# NIR-Spec-Analog-SCH_SH2__01.net
KiCad netlist of a schematic drawn in Altium Designer
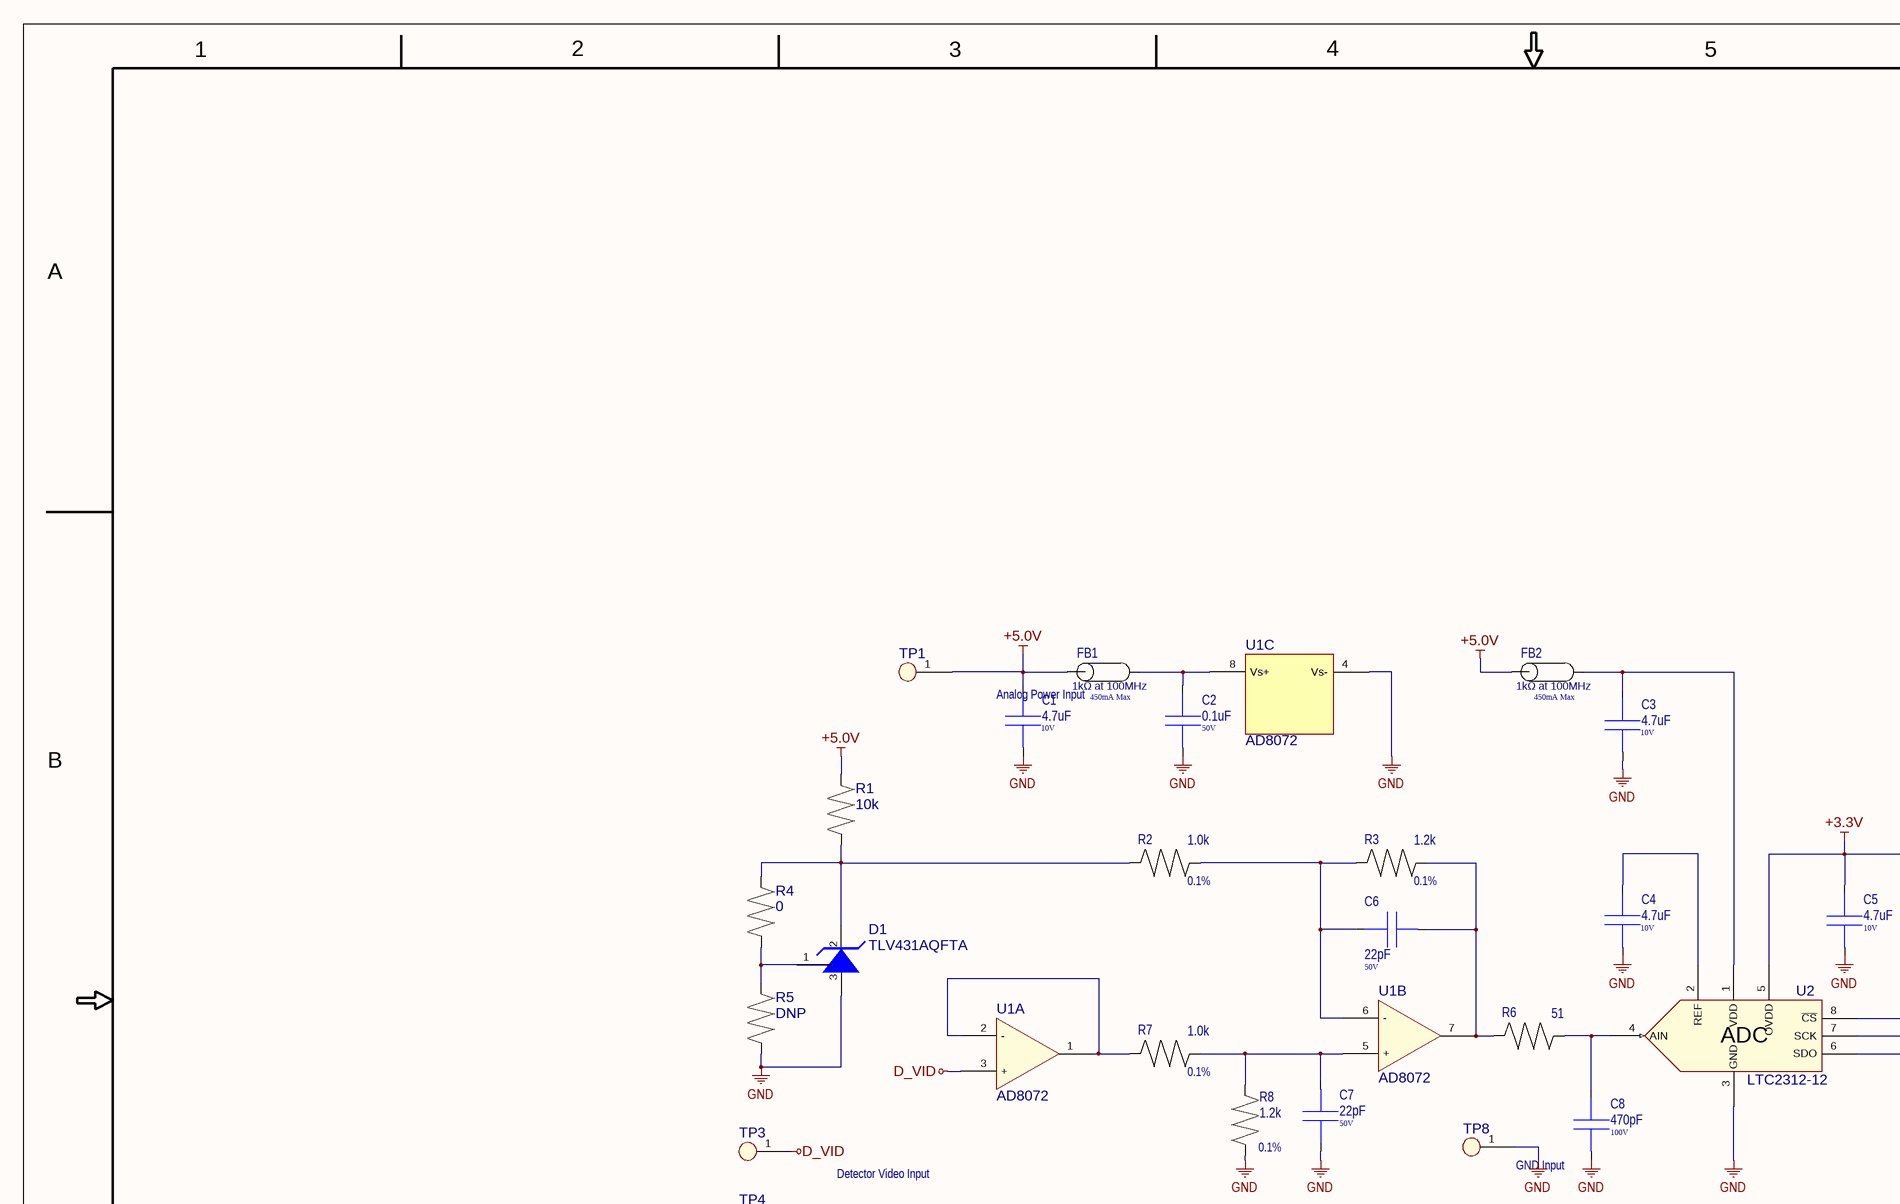
[diagram p0: NIR-Spec-Analog-SCH_SH2_(01).SchDoc, top left]
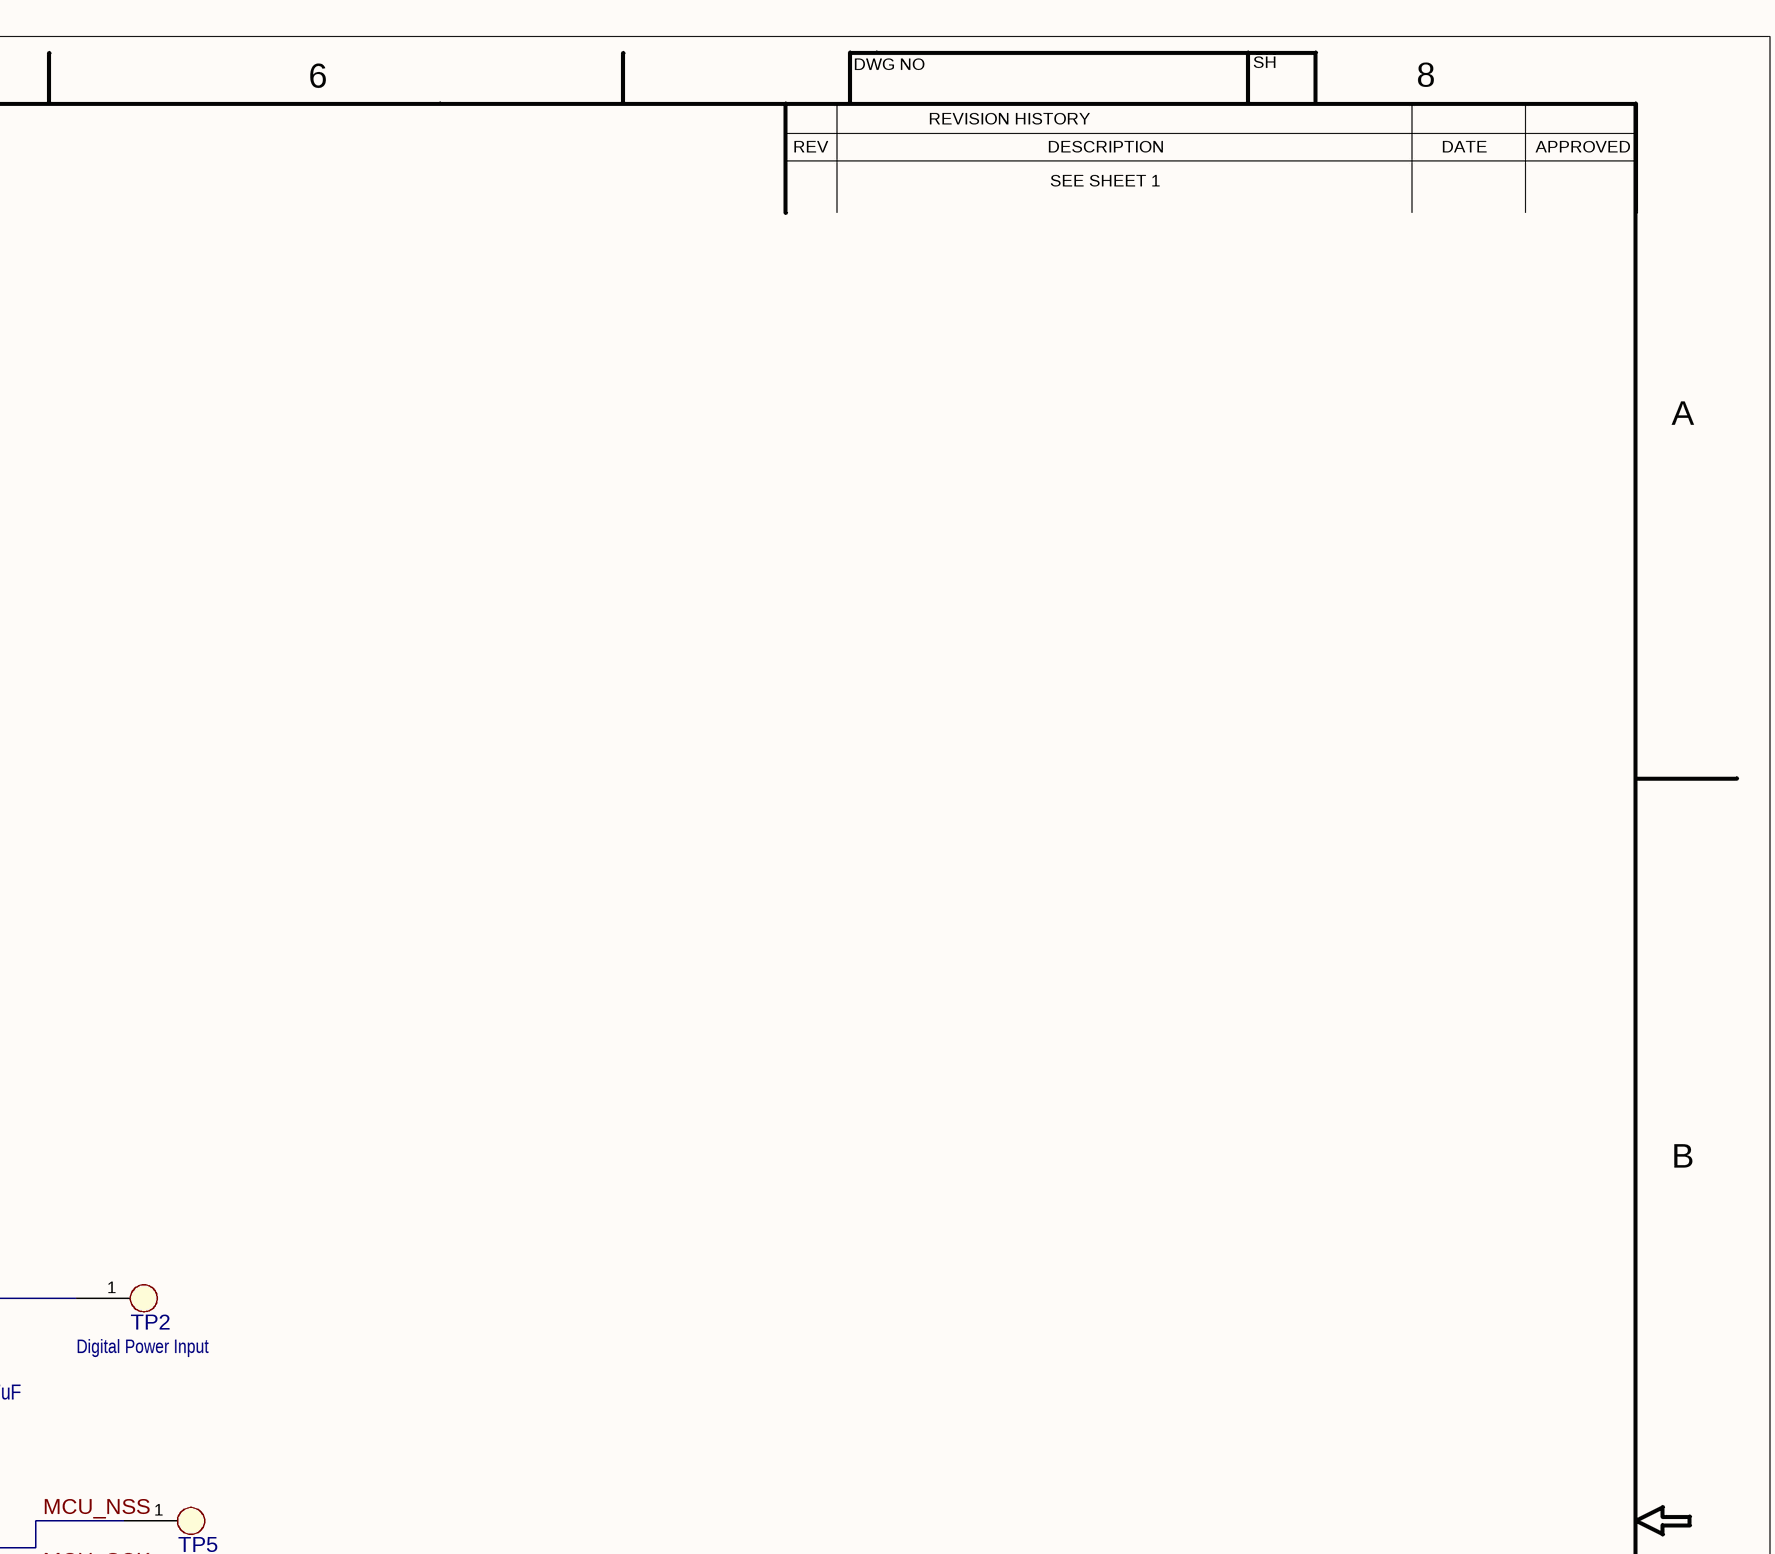
[diagram p1: NIR-Spec-Analog-SCH_SH2_(01).SchDoc, top right]
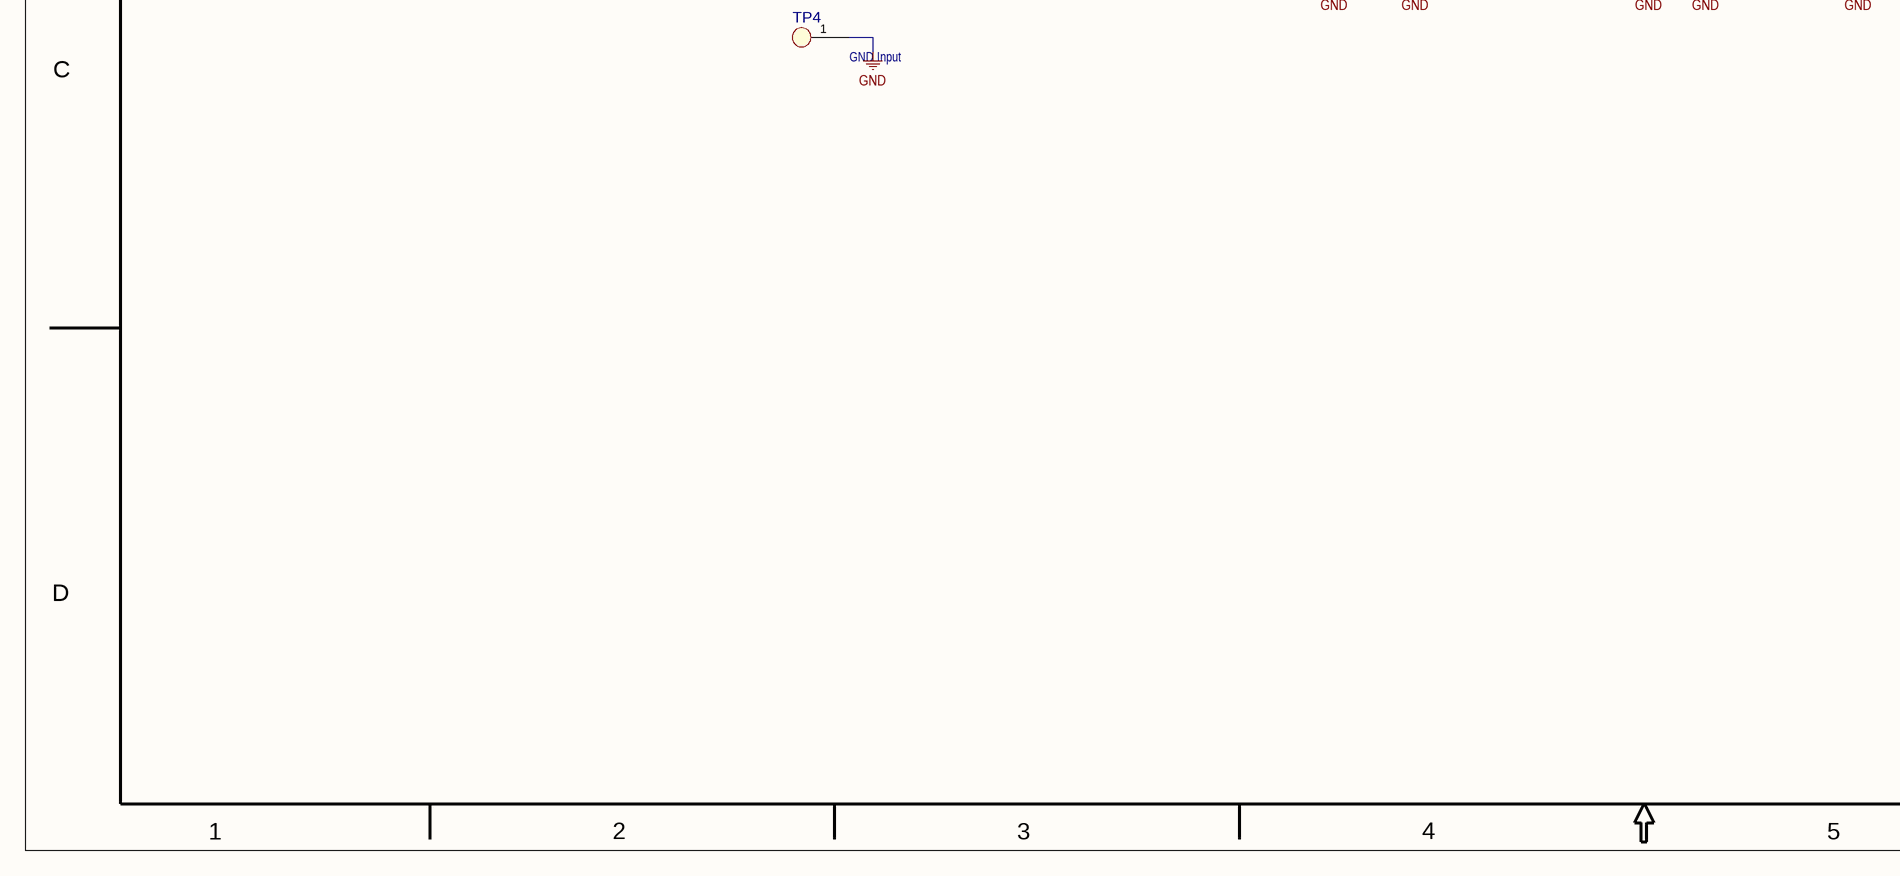
[diagram p2: NIR-Spec-Analog-SCH_SH2_(01).SchDoc, bottom left]
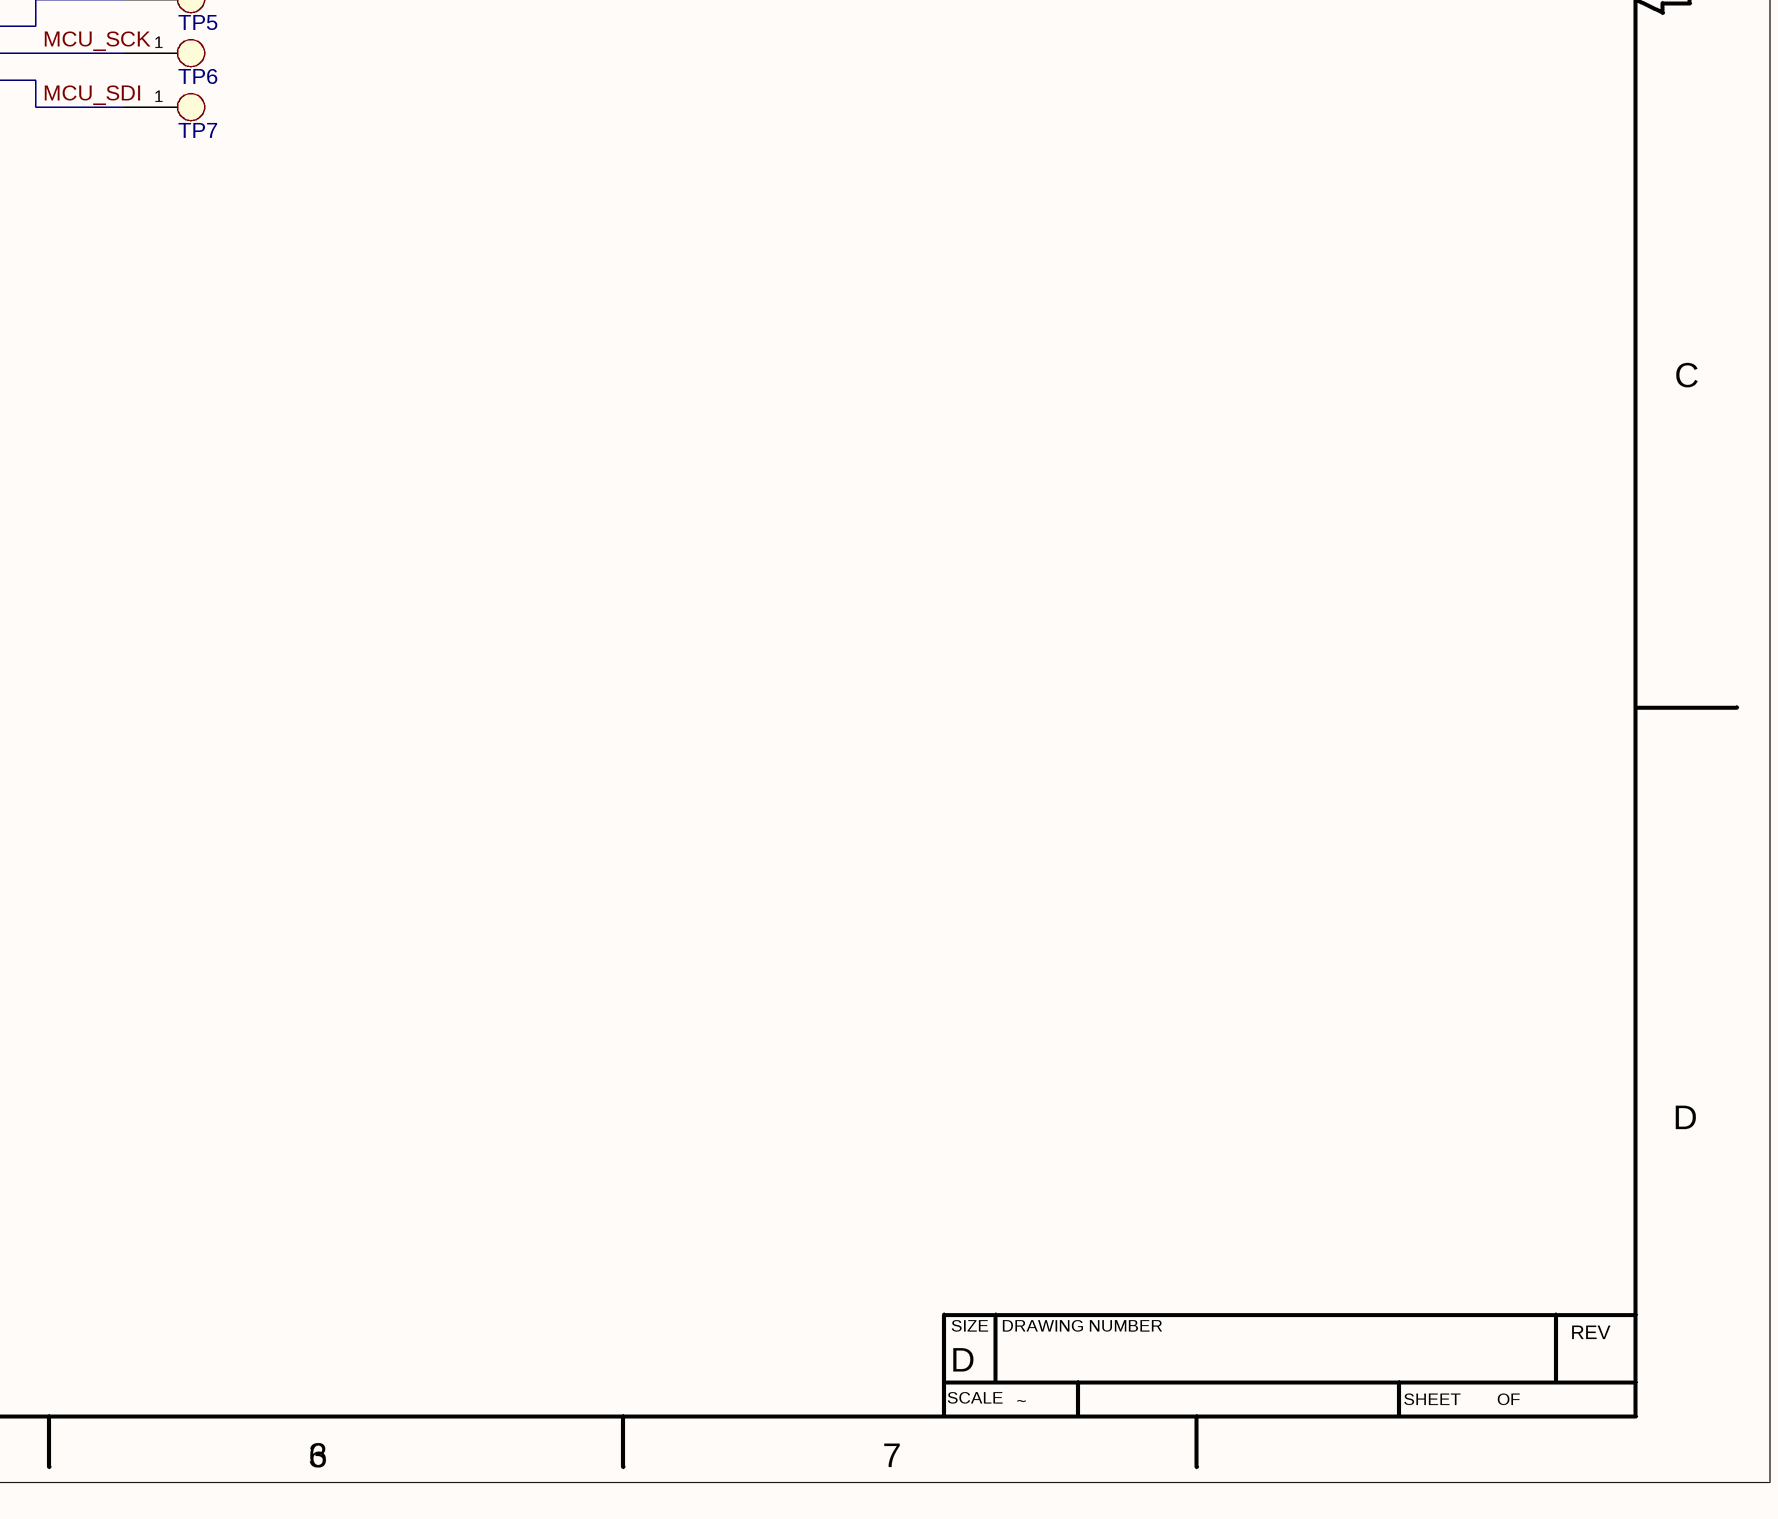
[diagram p3: NIR-Spec-Analog-SCH_SH2_(01).SchDoc, bottom right]

(export (version "E")
  (design (tool "Eeschema 10.0.6"))
  (components
    (comp (ref "C1")
      (value "4.7uF")
      (footprint "0402")
      (description "CAP CER 10UF 10V X6S 0603")
      (fields
        (field (name "PART NUMBER") "GRM188C81A106MA73D")
        (field (name "MANUFACTURER") "Murata Electronics")
        (field (name "VOLTAGE") "10V")
      )
      (libsource (lib "CAPACITORS") (part "CAP"))
    )
    (comp (ref "C2")
      (value "0.1uF")
      (footprint "0402")
      (description "CAP CER 0.1UF 50V X7R 0603")
      (fields
        (field (name "PART NUMBER") "C0603C104K5RAC3121")
        (field (name "MANUFACTURER") "KEMET")
        (field (name "VOLTAGE") "50V")
      )
      (libsource (lib "CAPACITORS") (part "CAP"))
    )
    (comp (ref "C3")
      (value "4.7uF")
      (footprint "0402")
      (description "CAP CER 10UF 10V X6S 0603")
      (fields
        (field (name "PART NUMBER") "GRM188C81A106MA73D")
        (field (name "MANUFACTURER") "Murata Electronics")
        (field (name "VOLTAGE") "10V")
      )
      (libsource (lib "CAPACITORS") (part "CAP"))
    )
    (comp (ref "C4")
      (value "4.7uF")
      (footprint "0402")
      (description "CAP CER 10UF 10V X6S 0603")
      (fields
        (field (name "PART NUMBER") "GRM188C81A106MA73D")
        (field (name "MANUFACTURER") "Murata Electronics")
        (field (name "VOLTAGE") "10V")
      )
      (libsource (lib "CAPACITORS") (part "CAP"))
    )
    (comp (ref "C5")
      (value "4.7uF")
      (footprint "0402")
      (description "CAP CER 10UF 10V X6S 0603")
      (fields
        (field (name "PART NUMBER") "GRM188C81A106MA73D")
        (field (name "MANUFACTURER") "Murata Electronics")
        (field (name "VOLTAGE") "10V")
      )
      (libsource (lib "CAPACITORS") (part "CAP"))
    )
    (comp (ref "C6")
      (value "22pF")
      (footprint "0402")
      (description "CAP CER 22PF NP0 50V 0603")
      (fields
        (field (name "PART NUMBER") "VJ0603A220KXAAC")
        (field (name "MANUFACTURER") "Vishay")
        (field (name "VOLTAGE") "50V")
      )
      (libsource (lib "CAPACITORS") (part "CAP"))
    )
    (comp (ref "C7")
      (value "22pF")
      (footprint "0402")
      (description "CAP CER 22PF NP0 50V 0603")
      (fields
        (field (name "PART NUMBER") "VJ0603A220KXAAC")
        (field (name "MANUFACTURER") "Vishay")
        (field (name "VOLTAGE") "50V")
      )
      (libsource (lib "CAPACITORS") (part "CAP"))
    )
    (comp (ref "C8")
      (value "470pF")
      (footprint "0402")
      (description "CAP CER 470PF NP0 100V 0603")
      (fields
        (field (name "PART NUMBER") "VJ0603A220KXAAC")
        (field (name "MANUFACTURER") "Vishay")
        (field (name "VOLTAGE") "100V")
      )
      (libsource (lib "CAPACITORS") (part "CAP"))
    )
    (comp (ref "D1")
      (value "TLV431AQFTA")
      (footprint "SOT-23-3")
      (description "Shunt Voltage Reference IC Adjustable 1.24V 18 VV ±1% 15 mA SOT-23-3")
      (fields (field (name "MANUFACTURER") "Diodes Incorporated"))
      (libsource (lib "TLV431AQFTA") (part "TLV431AQFTA"))
    )
    (comp (ref "FB1")
      (value "Ferrite_Bead")
      (footprint "0402")
      (description "Ferrite Beads 1000 OHM 25%")
      (fields
        (field (name "MANUFACTURER") "Murata Electronics")
        (field (name "PART NUMBER") "BLM18AG102SH1D")
        (field (name "RATED CURRENT") "450mA Max")
        (field (name "IMPEDANCE") "1kΩ at 100MHz")
      )
      (libsource (lib "Ferrite_Beads") (part "Ferrite_Bead"))
    )
    (comp (ref "FB2")
      (value "Ferrite_Bead")
      (footprint "0402")
      (description "Ferrite Beads 1000 OHM 25%")
      (fields
        (field (name "MANUFACTURER") "Murata Electronics")
        (field (name "PART NUMBER") "BLM18AG102SH1D")
        (field (name "RATED CURRENT") "450mA Max")
        (field (name "IMPEDANCE") "1kΩ at 100MHz")
      )
      (libsource (lib "Ferrite_Beads") (part "Ferrite_Bead"))
    )
    (comp (ref "R1")
      (value "10k")
      (footprint "0402")
      (description "RESISTOR")
      (libsource (lib "RESISTORS") (part "RES"))
    )
    (comp (ref "R2")
      (value "1.0k")
      (footprint "0402")
      (fields (field (name "PART NUMBER") "CPF-A-0603B1K0E") (field (name "MANUFACTURER") "TE Connectivity"))
      (libsource (lib "RESISTORS") (part "RES"))
    )
    (comp (ref "R3")
      (value "1.2k")
      (footprint "0402")
      (description "Thin Film Resistors - SMD 0603 249ohms 25ppm 0.5%")
      (fields (field (name "PART NUMBER") "ERA-3AED2490V") (field (name "MANUFACTURER") "Panasonic"))
      (libsource (lib "RESISTORS") (part "RES"))
    )
    (comp (ref "R4")
      (value "0")
      (footprint "0603")
      (description "RESISTOR")
      (libsource (lib "RESISTORS") (part "RES"))
    )
    (comp (ref "R5")
      (value "DNP")
      (footprint "0603")
      (description "RESISTOR")
      (libsource (lib "RESISTORS") (part "RES"))
    )
    (comp (ref "R6")
      (value "51")
      (footprint "0402")
      (description "Thin Film Resistors - SMD .1W 51ohm 1% 0603")
      (fields (field (name "PART NUMBER") "MCT06030C5109FP500") (field (name "MANUFACTURER") "Vishay"))
      (libsource (lib "RESISTORS") (part "RES"))
    )
    (comp (ref "R7")
      (value "1.0k")
      (footprint "0402")
      (fields (field (name "PART NUMBER") "CPF-A-0603B1K0E") (field (name "MANUFACTURER") "TE Connectivity"))
      (libsource (lib "RESISTORS") (part "RES"))
    )
    (comp (ref "R8")
      (value "1.2k")
      (footprint "0402")
      (description "Thin Film Resistors - SMD 0603 249ohms 25ppm 0.5%")
      (fields (field (name "PART NUMBER") "ERA-3AED2490V") (field (name "MANUFACTURER") "Panasonic"))
      (libsource (lib "RESISTORS") (part "RES"))
    )
    (comp (ref "TP1")
      (value "TEST POINT")
      (footprint "30x40 TP")
      (libsource (lib "TestPoint") (part "TEST POINT"))
    )
    (comp (ref "TP2")
      (value "TEST POINT")
      (footprint "30x40 TP")
      (libsource (lib "TestPoint") (part "TEST POINT"))
    )
    (comp (ref "TP3")
      (value "TEST POINT")
      (footprint "30x40 TP")
      (libsource (lib "TestPoint") (part "TEST POINT"))
    )
    (comp (ref "TP4")
      (value "TEST POINT")
      (footprint "30x40 TP")
      (libsource (lib "TestPoint") (part "TEST POINT"))
    )
    (comp (ref "TP5")
      (value "TEST POINT")
      (footprint "30x40 TP")
      (libsource (lib "TestPoint") (part "TEST POINT"))
    )
    (comp (ref "TP6")
      (value "TEST POINT")
      (footprint "30x40 TP")
      (libsource (lib "TestPoint") (part "TEST POINT"))
    )
    (comp (ref "TP7")
      (value "TEST POINT")
      (footprint "30x40 TP")
      (libsource (lib "TestPoint") (part "TEST POINT"))
    )
    (comp (ref "TP8")
      (value "TEST POINT")
      (footprint "30x40 TP")
      (libsource (lib "TestPoint") (part "TEST POINT"))
    )
    (comp (ref "U1")
      (value "AD8072")
      (footprint "SOIC_8")
      (description "IC OPAMP VIDEO DUAL 8MSOP")
      (fields (field (name "PART NUMBER") "AD8072ARMZ") (field (name "MANUFACTURER") "Analog Devices Inc."))
      (libsource (lib "Op_Amps") (part "AD8072"))
    )
    (comp (ref "U2")
      (value "LTC2312-12")
      (footprint "TSOT-23-8")
      (description "IC ADC 12BIT SAR TSOT23-8")
      (fields
        (field (name "MANUFACTURER") "Linear Technology")
        (field (name "PART NUMBER") "LTC2314xTS8-14#TRMPBF")
      )
      (libsource (lib "Converters") (part "LTC2314xTS8-14#TRMPBF"))
    )
  )
  (nets
    (net (code "1") (name "+3.3V") (class "Default")
      (node (ref "C5") (pin "2") (pinfunction "2_2") (pintype "passive"))
      (node (ref "TP2") (pin "1") (pinfunction "1_1") (pintype "passive"))
      (node (ref "U2") (pin "5") (pinfunction "OVDD_5") (pintype "power_in"))
    )
    (net (code "2") (name "+5.0V") (class "Default")
      (node (ref "C1") (pin "2") (pinfunction "2_2") (pintype "passive"))
      (node (ref "FB1") (pin "1") (pinfunction "1_1") (pintype "passive"))
      (node (ref "FB2") (pin "1") (pinfunction "1_1") (pintype "passive"))
      (node (ref "R1") (pin "1") (pinfunction "1_1") (pintype "passive"))
      (node (ref "TP1") (pin "1") (pinfunction "1_1") (pintype "passive"))
    )
    (net (code "3") (name "/MCU_NSS") (class "Default")
      (node (ref "TP5") (pin "1") (pinfunction "1_1") (pintype "passive"))
      (node (ref "U2") (pin "8") (pinfunction "~{CS}_8") (pintype "passive"))
    )
    (net (code "4") (name "/MCU_SCK") (class "Default")
      (node (ref "TP6") (pin "1") (pinfunction "1_1") (pintype "passive"))
      (node (ref "U2") (pin "7") (pinfunction "SCK_7") (pintype "passive"))
    )
    (net (code "5") (name "/MCU_SDI") (class "Default")
      (node (ref "TP7") (pin "1") (pinfunction "1_1") (pintype "passive"))
      (node (ref "U2") (pin "6") (pinfunction "SDO_6") (pintype "passive"))
    )
    (net (code "6") (name "D_VID") (class "Default")
      (node (ref "TP3") (pin "1") (pinfunction "1_1") (pintype "passive"))
      (node (ref "U1") (pin "3") (pinfunction "+_3") (pintype "passive"))
    )
    (net (code "7") (name "GND") (class "Default")
      (node (ref "C1") (pin "1") (pinfunction "1_1") (pintype "passive"))
      (node (ref "C2") (pin "1") (pinfunction "1_1") (pintype "passive"))
      (node (ref "C3") (pin "1") (pinfunction "1_1") (pintype "passive"))
      (node (ref "C4") (pin "1") (pinfunction "1_1") (pintype "passive"))
      (node (ref "C5") (pin "1") (pinfunction "1_1") (pintype "passive"))
      (node (ref "C7") (pin "2") (pinfunction "2_2") (pintype "passive"))
      (node (ref "C8") (pin "1") (pinfunction "1_1") (pintype "passive"))
      (node (ref "D1") (pin "3") (pinfunction "A_3") (pintype "passive"))
      (node (ref "R5") (pin "2") (pinfunction "2_2") (pintype "passive"))
      (node (ref "R8") (pin "1") (pinfunction "1_1") (pintype "passive"))
      (node (ref "TP4") (pin "1") (pinfunction "1_1") (pintype "passive"))
      (node (ref "TP8") (pin "1") (pinfunction "1_1") (pintype "passive"))
      (node (ref "U1") (pin "4") (pinfunction "Vs-_4") (pintype "power_in"))
      (node (ref "U2") (pin "3") (pinfunction "GND_3") (pintype "power_in"))
    )
    (net (code "8") (name "Net-(D1-K)") (class "Default")
      (node (ref "D1") (pin "2") (pinfunction "K_2") (pintype "passive"))
      (node (ref "R1") (pin "2") (pinfunction "2_2") (pintype "passive"))
      (node (ref "R2") (pin "1") (pinfunction "1_1") (pintype "passive"))
      (node (ref "R4") (pin "1") (pinfunction "1_1") (pintype "passive"))
    )
    (net (code "9") (name "Net-(D1-REF)") (class "Default")
      (node (ref "D1") (pin "1") (pinfunction "REF_1") (pintype "power_in"))
      (node (ref "R4") (pin "2") (pinfunction "2_2") (pintype "passive"))
      (node (ref "R5") (pin "1") (pinfunction "1_1") (pintype "passive"))
    )
    (net (code "10") (name "Net-(U1A--)") (class "Default")
      (node (ref "R7") (pin "1") (pinfunction "1_1") (pintype "passive"))
      (node (ref "U1") (pin "1") (pinfunction "OUT_1") (pintype "passive"))
      (node (ref "U1") (pin "2") (pinfunction "-_2") (pintype "passive"))
    )
    (net (code "11") (name "Net-(U1B-+)") (class "Default")
      (node (ref "C7") (pin "1") (pinfunction "1_1") (pintype "passive"))
      (node (ref "R7") (pin "2") (pinfunction "2_2") (pintype "passive"))
      (node (ref "R8") (pin "2") (pinfunction "2_2") (pintype "passive"))
      (node (ref "U1") (pin "5") (pinfunction "+_5") (pintype "passive"))
    )
    (net (code "12") (name "Net-(U1B--)") (class "Default")
      (node (ref "C6") (pin "2") (pinfunction "2_2") (pintype "passive"))
      (node (ref "R2") (pin "2") (pinfunction "2_2") (pintype "passive"))
      (node (ref "R3") (pin "1") (pinfunction "1_1") (pintype "passive"))
      (node (ref "U1") (pin "6") (pinfunction "-_6") (pintype "passive"))
    )
    (net (code "13") (name "Net-(U1B-OUT)") (class "Default")
      (node (ref "C6") (pin "1") (pinfunction "1_1") (pintype "passive"))
      (node (ref "R3") (pin "2") (pinfunction "2_2") (pintype "passive"))
      (node (ref "R6") (pin "1") (pinfunction "1_1") (pintype "passive"))
      (node (ref "U1") (pin "7") (pinfunction "OUT_7") (pintype "passive"))
    )
    (net (code "14") (name "Net-(U1C-Vs+)") (class "Default")
      (node (ref "C2") (pin "2") (pinfunction "2_2") (pintype "passive"))
      (node (ref "FB1") (pin "2") (pinfunction "2_2") (pintype "passive"))
      (node (ref "U1") (pin "8") (pinfunction "Vs+_8") (pintype "power_in"))
    )
    (net (code "15") (name "Net-(U2-AIN)") (class "Default")
      (node (ref "C8") (pin "2") (pinfunction "2_2") (pintype "passive"))
      (node (ref "R6") (pin "2") (pinfunction "2_2") (pintype "passive"))
      (node (ref "U2") (pin "4") (pinfunction "AIN_4") (pintype "input"))
    )
    (net (code "16") (name "Net-(U2-REF)") (class "Default")
      (node (ref "C4") (pin "2") (pinfunction "2_2") (pintype "passive"))
      (node (ref "U2") (pin "2") (pinfunction "REF_2") (pintype "power_in"))
    )
    (net (code "17") (name "Net-(U2-VDD)") (class "Default")
      (node (ref "C3") (pin "2") (pinfunction "2_2") (pintype "passive"))
      (node (ref "FB2") (pin "2") (pinfunction "2_2") (pintype "passive"))
      (node (ref "U2") (pin "1") (pinfunction "VDD_1") (pintype "power_in"))
    )
  )
)
